# resetCircuit.net
KiCad netlist of a schematic drawn in EAGLE
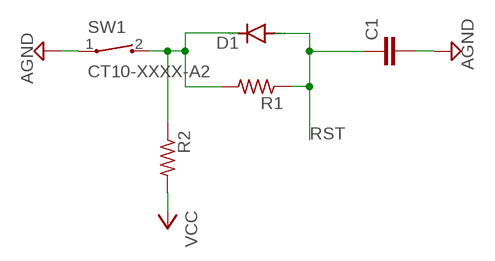
[diagram p0: schematic, sheet 1]

(export (version "E")
  (design (tool "Eeschema 10.0.6"))
  (components
    (comp (ref "C1")
      (value "C-EU01005")
      (footprint "eagle-import:C01005")
      (libsource (lib "eagle-import") (part "C-EU01005"))
    )
    (comp (ref "D1")
      (value "DIODE-DO-214AC")
      (footprint "eagle-import:DO-214AC")
      (libsource (lib "eagle-import") (part "DIODE-DO-214AC"))
    )
    (comp (ref "R1")
      (value "R-US_01005")
      (footprint "eagle-import:R01005")
      (libsource (lib "eagle-import") (part "R-US_01005"))
    )
    (comp (ref "R2")
      (value "R-US_01005")
      (footprint "eagle-import:R01005")
      (libsource (lib "eagle-import") (part "R-US_01005"))
    )
    (comp (ref "SW1")
      (value "CT10-XXXX-A2")
      (footprint "eagle-import:CT10-XXXX-A2")
      (libsource (lib "eagle-import") (part "CT10-XXXX-A2"))
    )
  )
  (nets
    (net (code "1") (name "/RST") (class "Default")
      (node (ref "C1") (pin "1") (pinfunction "1_1") (pintype "passive"))
      (node (ref "D1") (pin "A") (pinfunction "A_A") (pintype "passive"))
      (node (ref "R1") (pin "1") (pinfunction "1_1") (pintype "passive"))
    )
    (net (code "2") (name "AGND") (class "Default")
      (node (ref "C1") (pin "2") (pinfunction "2_2") (pintype "passive"))
      (node (ref "SW1") (pin "1") (pinfunction "1_1") (pintype "passive"))
    )
    (net (code "3") (name "Net-(D1-PadC)") (class "Default")
      (node (ref "D1") (pin "C") (pinfunction "C_C") (pintype "passive"))
      (node (ref "R1") (pin "2") (pinfunction "2_2") (pintype "passive"))
      (node (ref "R2") (pin "1") (pinfunction "1_1") (pintype "passive"))
      (node (ref "SW1") (pin "2") (pinfunction "2_2") (pintype "passive"))
    )
    (net (code "4") (name "VCC") (class "Default")
      (node (ref "R2") (pin "2") (pinfunction "2_2") (pintype "passive"))
    )
  )
)
